# codec_CS42448_rev_A.net
KiCad netlist of a schematic drawn in EAGLE
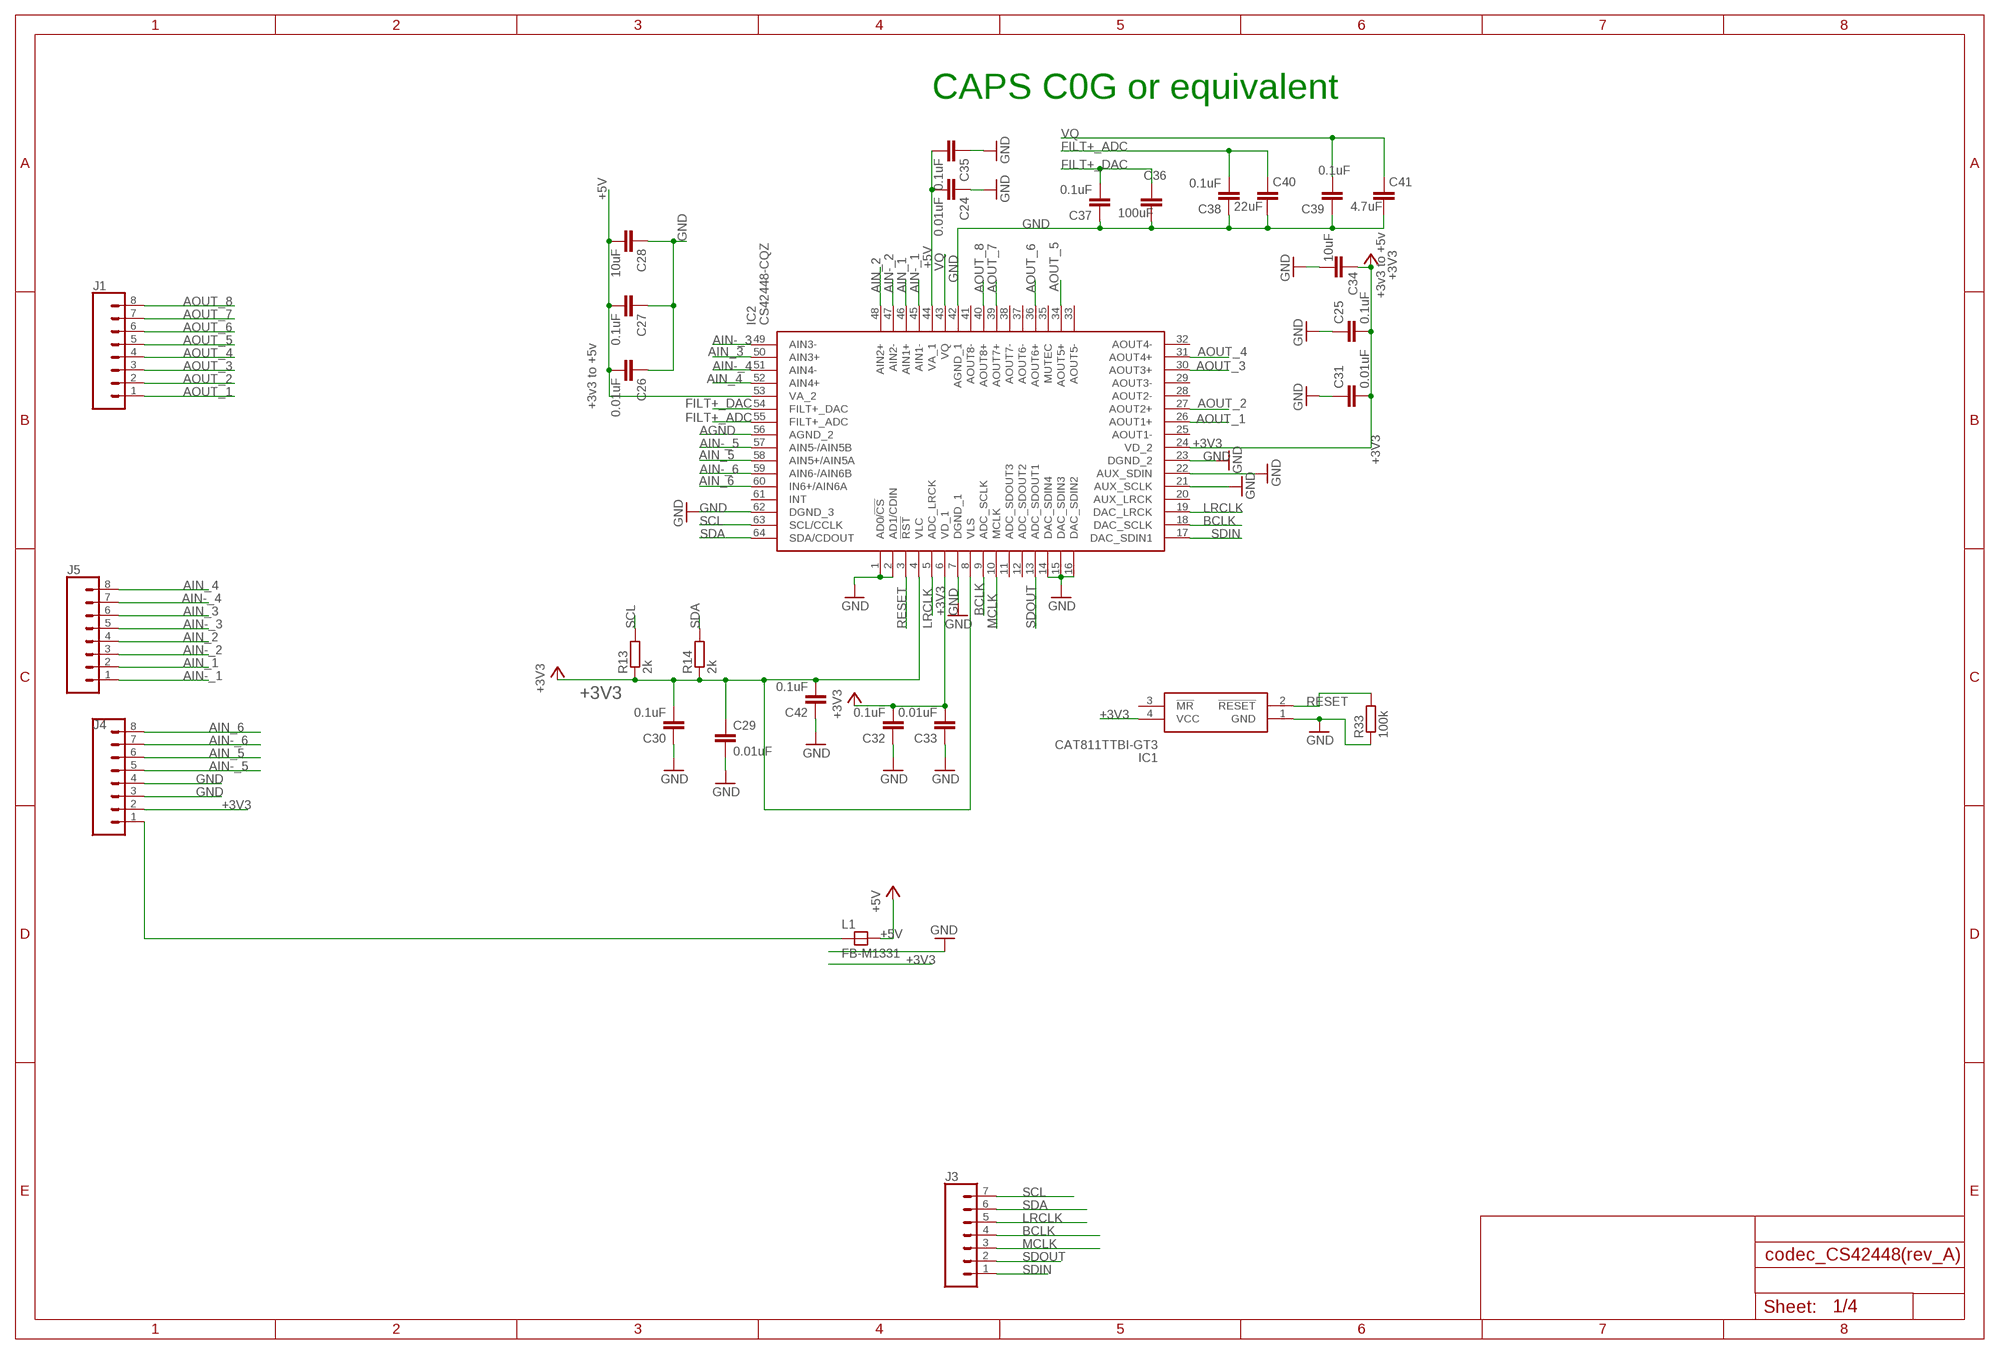
[diagram p0: schematic, sheet 1]
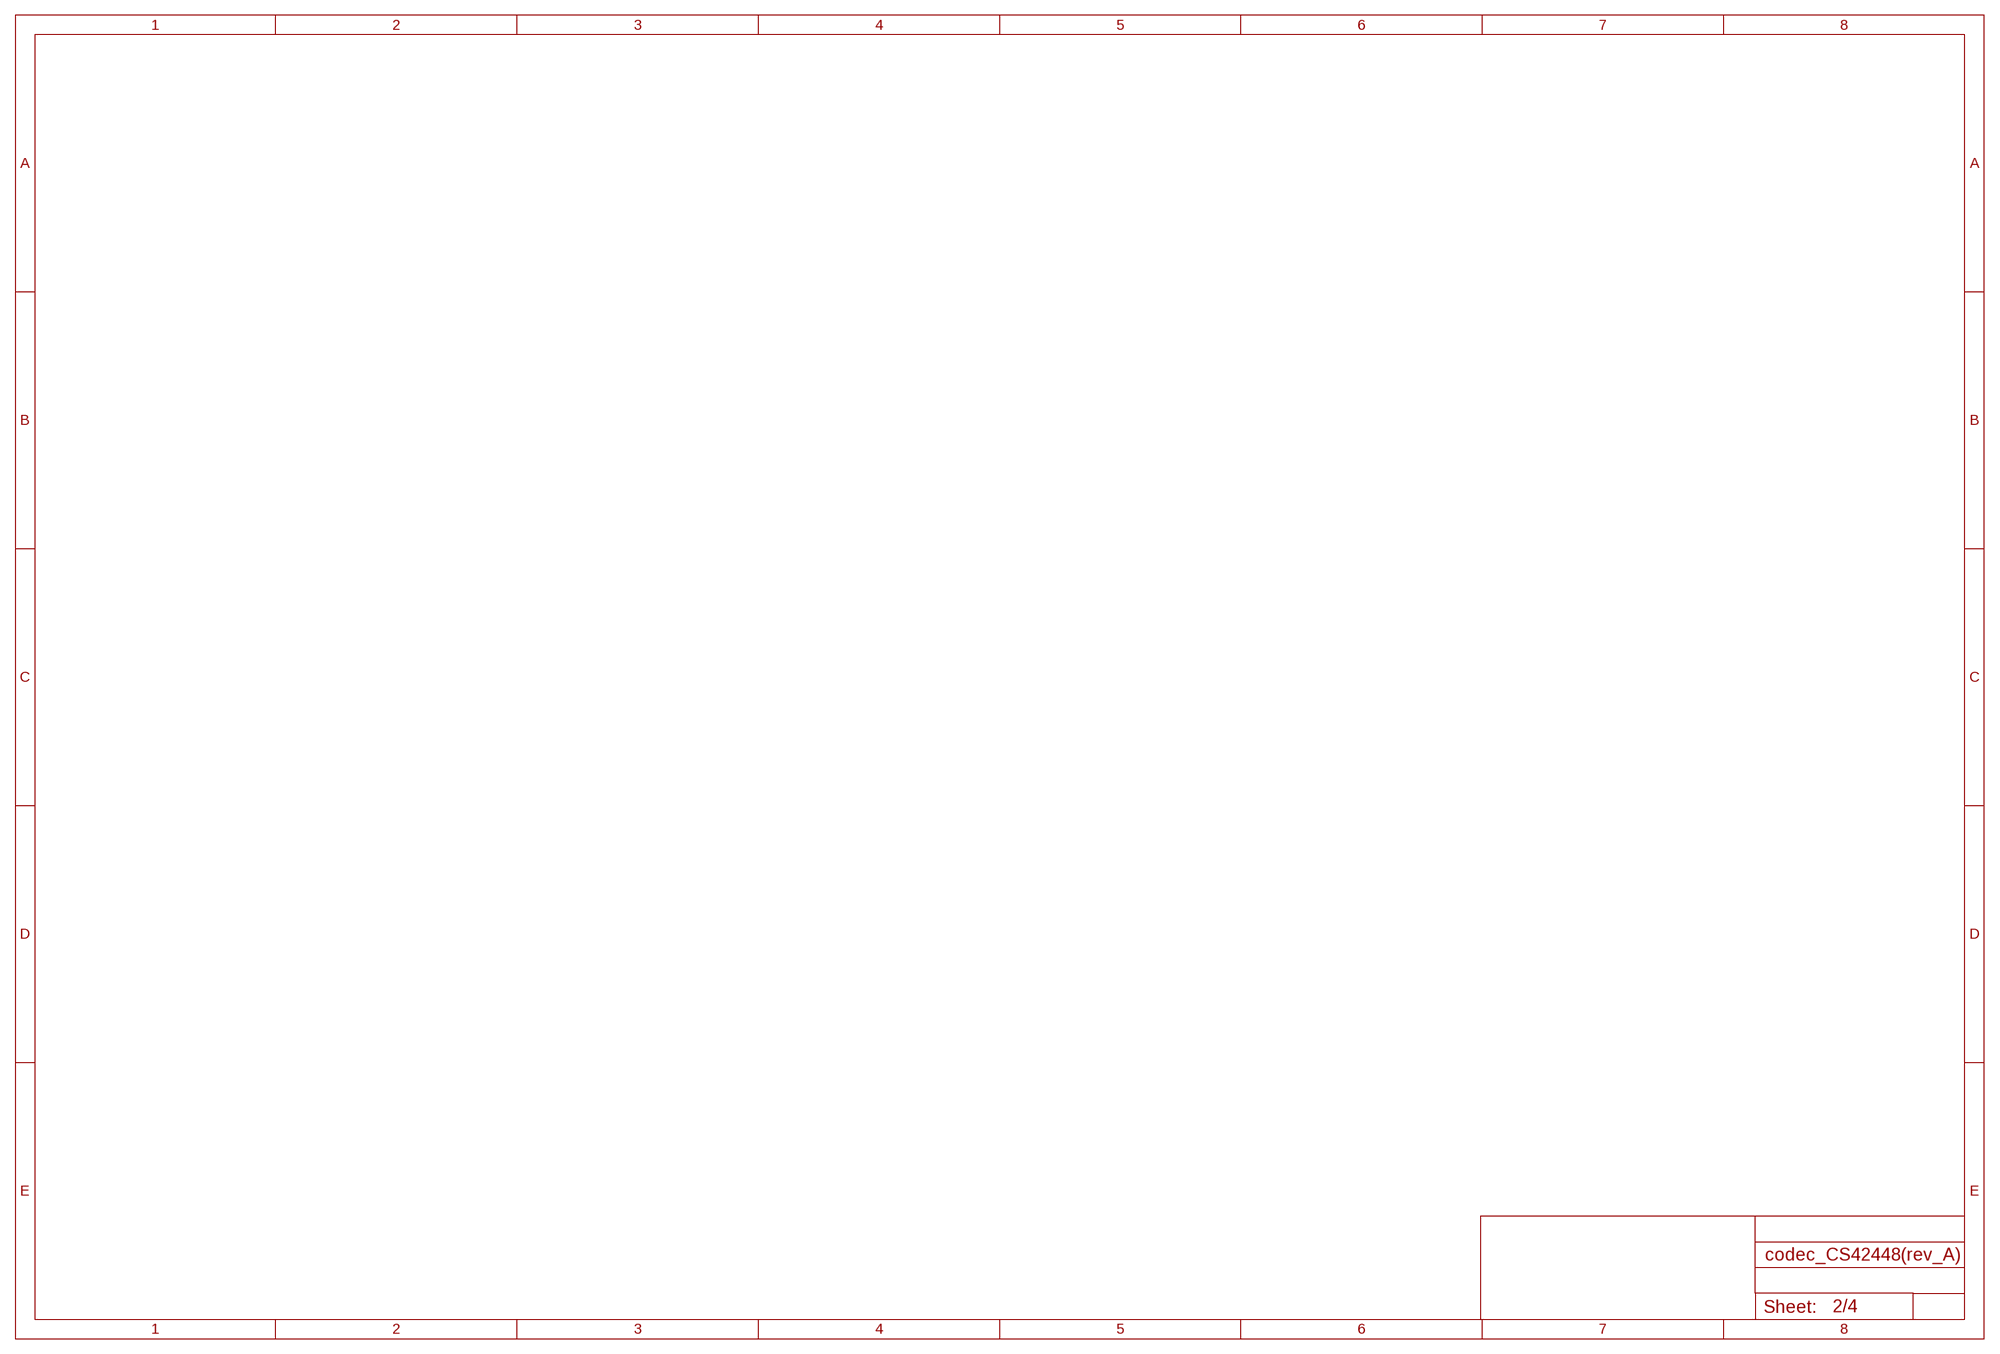
[diagram p1: schematic, sheet 2]
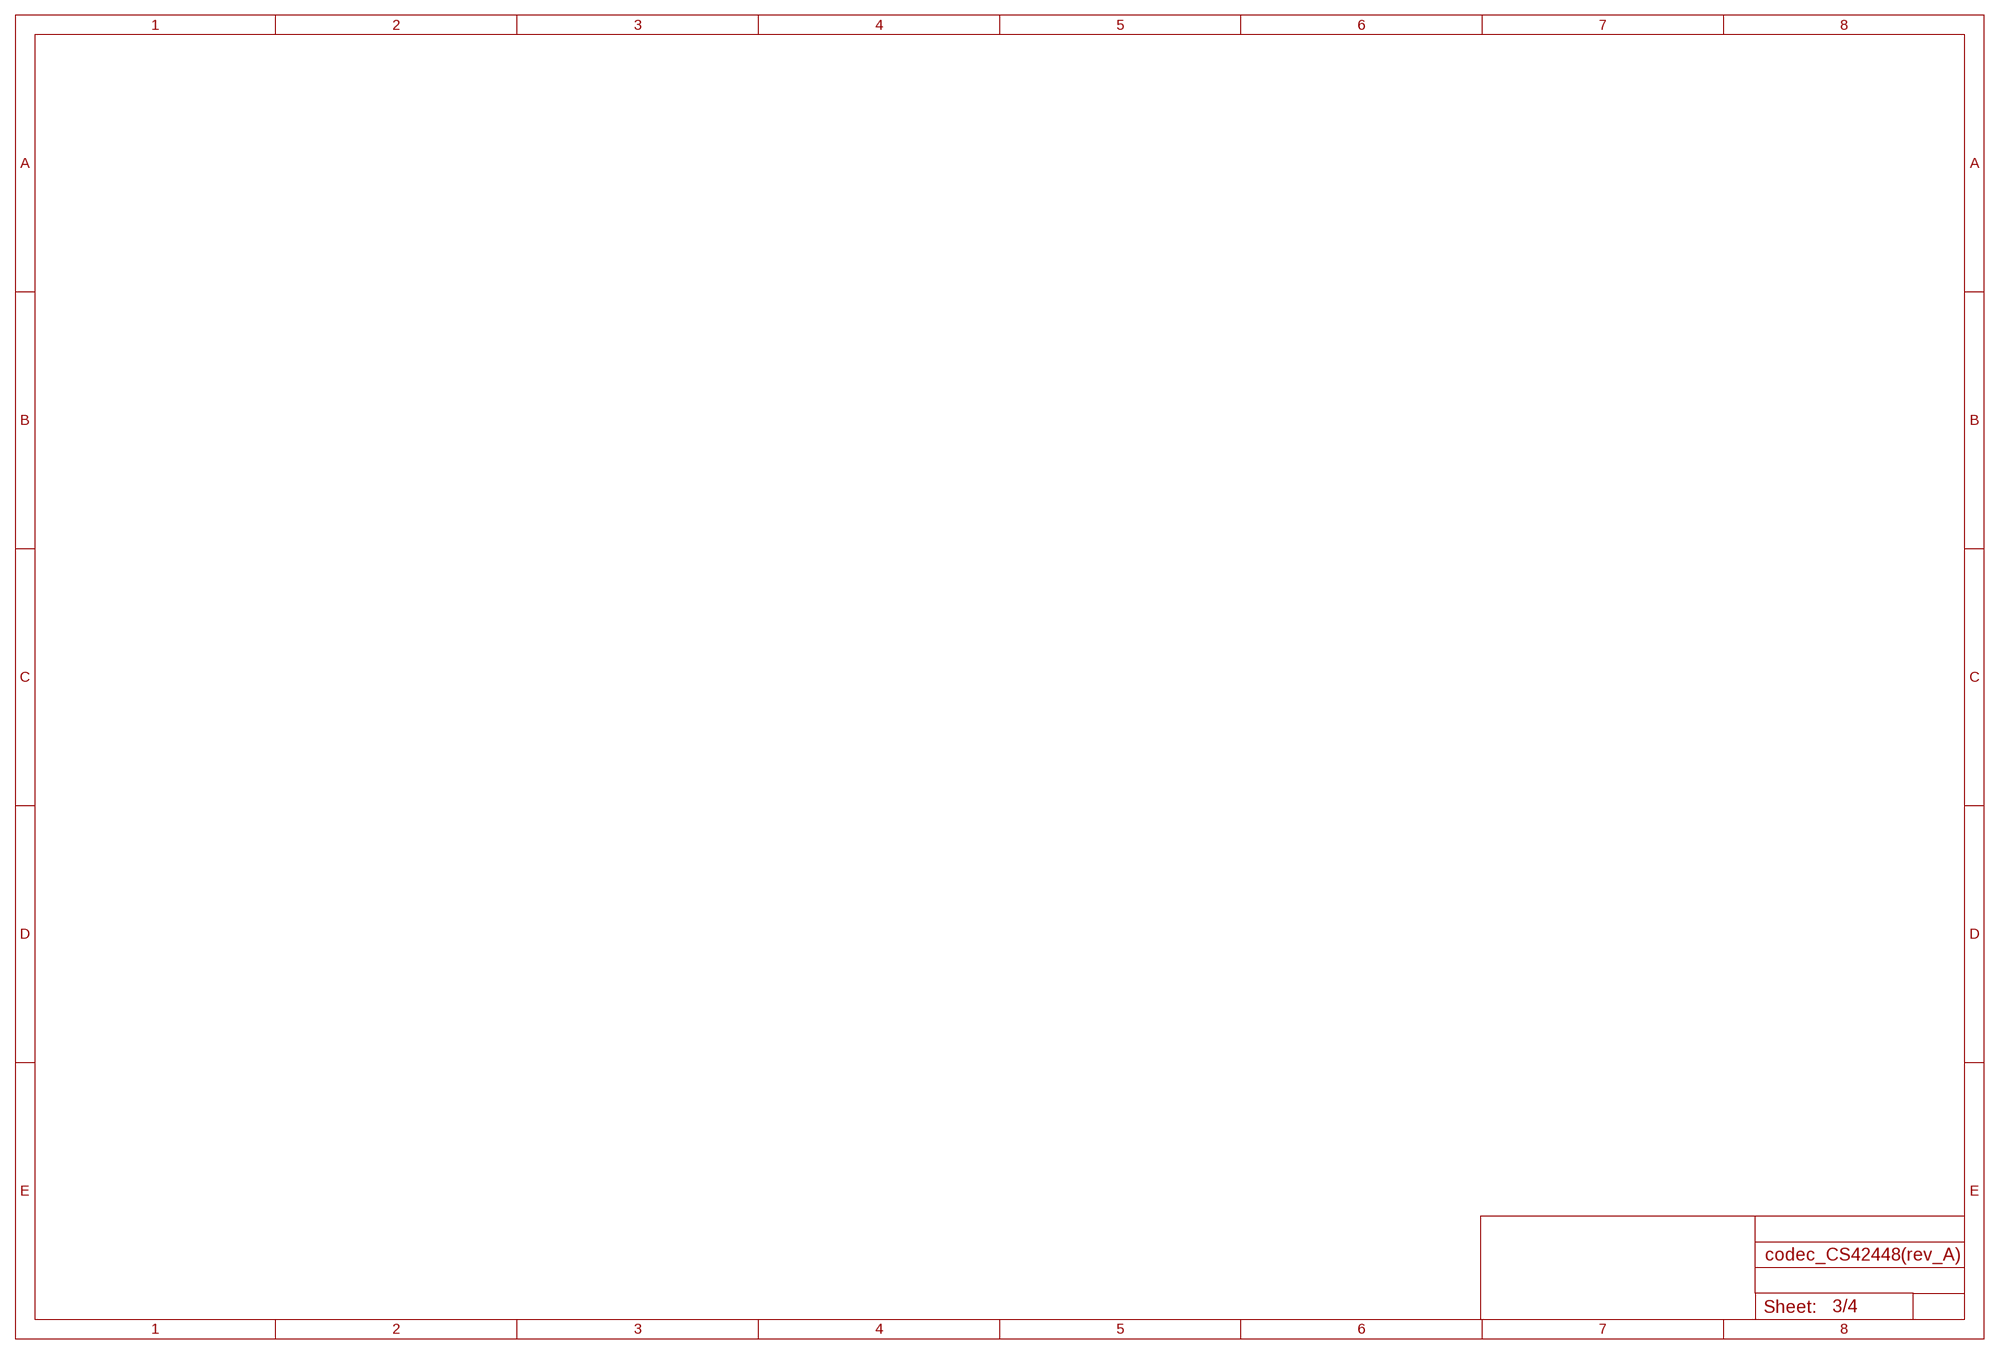
[diagram p2: schematic, sheet 3]
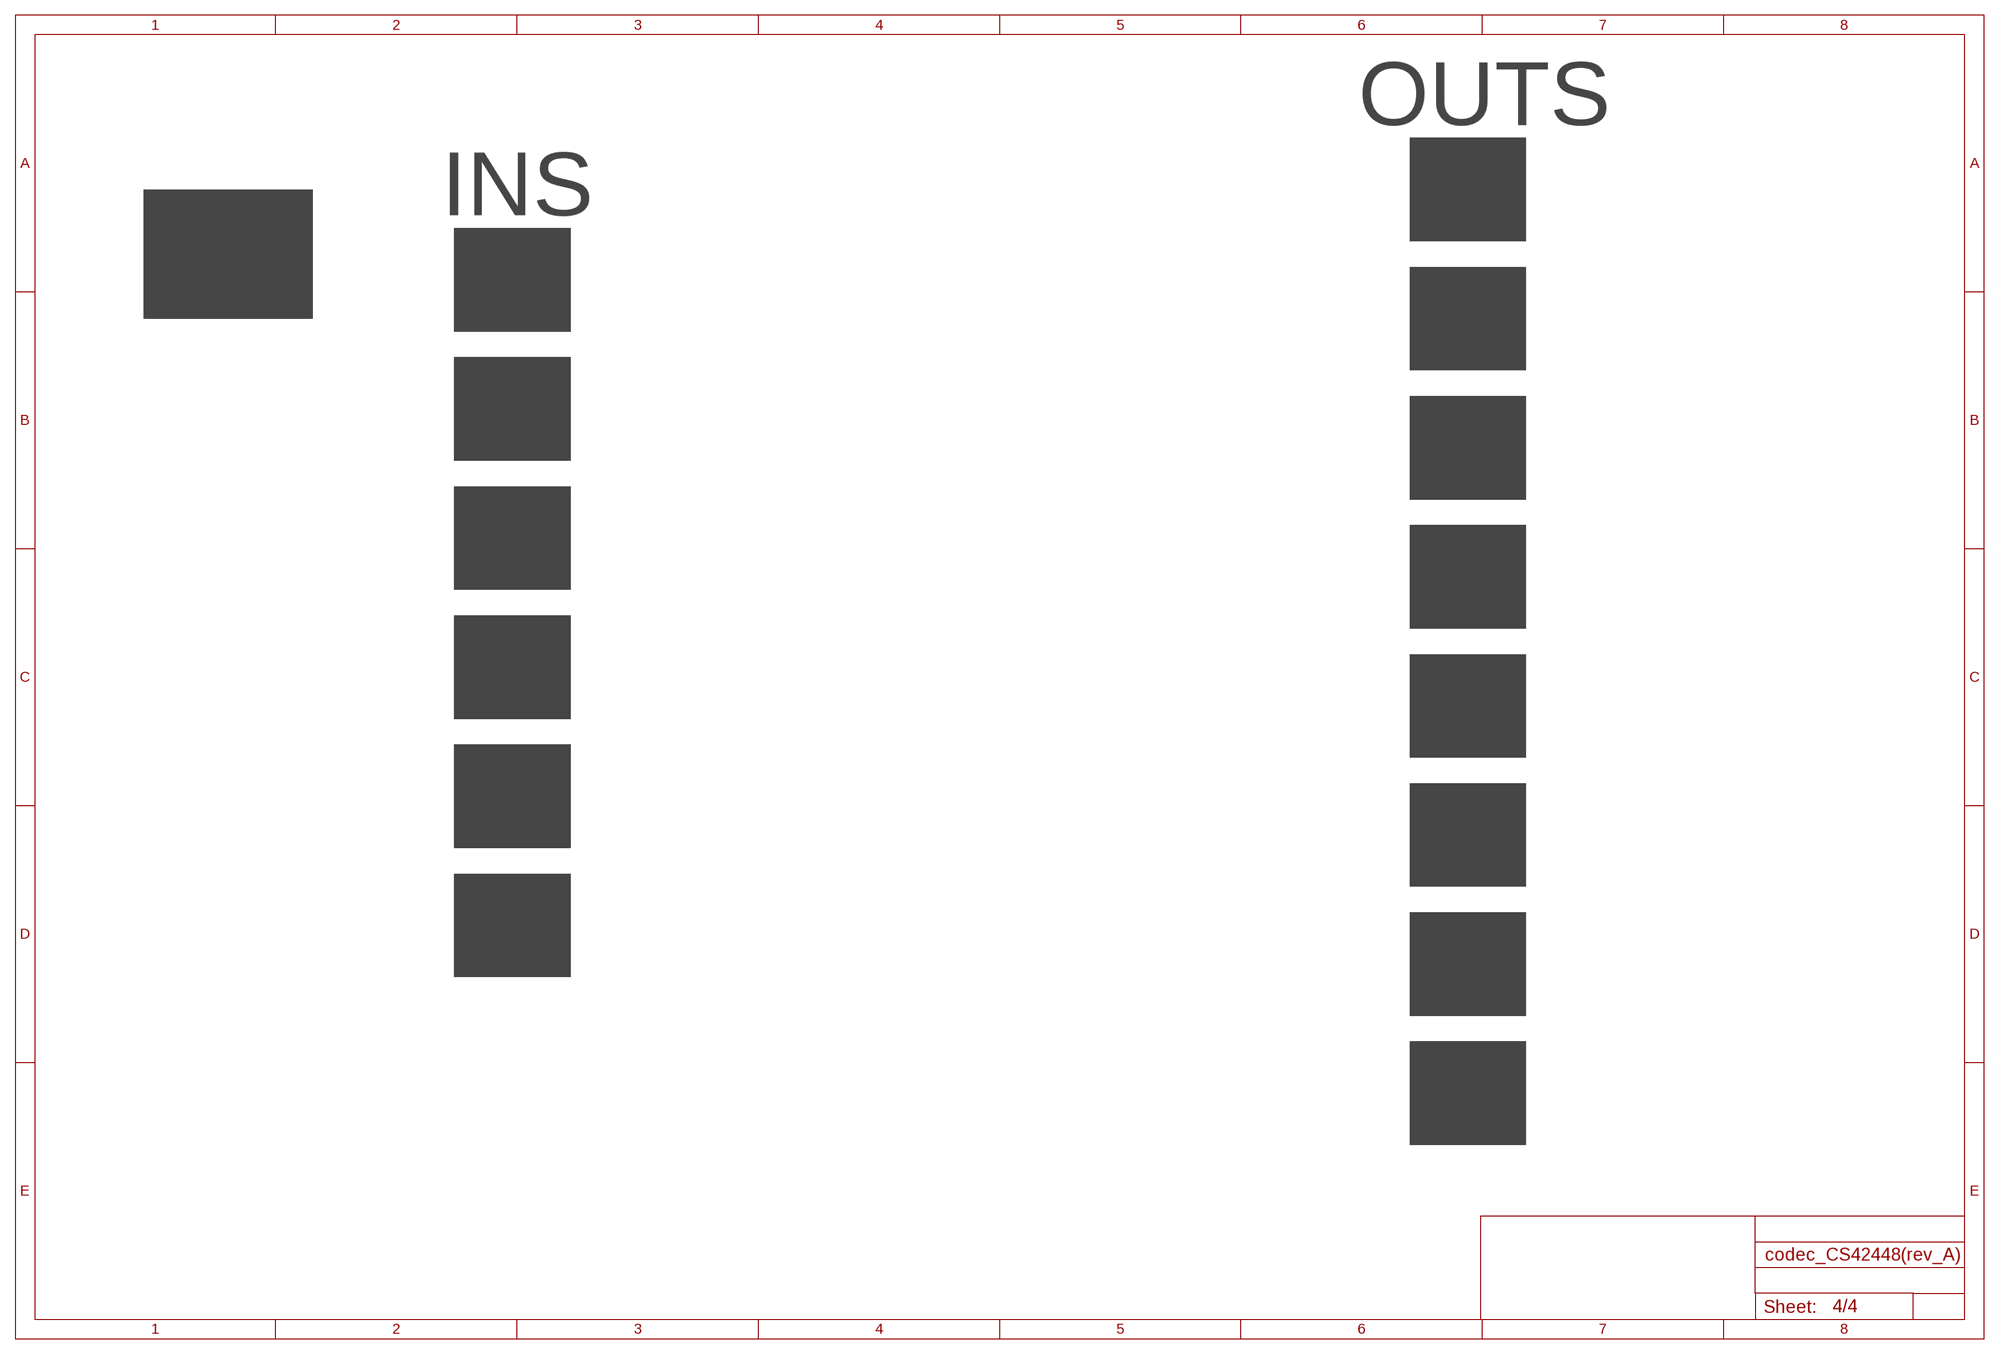
[diagram p3: schematic, sheet 4]

(export (version "E")
  (design (tool "Eeschema 10.0.6"))
  (components
    (comp (ref "C24")
      (value "0.01uF")
      (footprint "eagle-import:C0805")
      (libsource (lib "eagle-import") (part "C-EUC0805"))
    )
    (comp (ref "C25")
      (value "0.1uF")
      (footprint "eagle-import:C0603")
      (libsource (lib "eagle-import") (part "C-EUC0603"))
    )
    (comp (ref "C26")
      (value "0.01uF")
      (footprint "eagle-import:C0805")
      (libsource (lib "eagle-import") (part "C-EUC0805"))
    )
    (comp (ref "C27")
      (value "0.1uF")
      (footprint "eagle-import:C0603")
      (libsource (lib "eagle-import") (part "C-EUC0603"))
    )
    (comp (ref "C28")
      (value "10uF")
      (footprint "eagle-import:C0805")
      (libsource (lib "eagle-import") (part "C-EUC0805"))
    )
    (comp (ref "C29")
      (value "0.01uF")
      (footprint "eagle-import:C0805")
      (libsource (lib "eagle-import") (part "C-EUC0805"))
    )
    (comp (ref "C30")
      (value "0.1uF")
      (footprint "eagle-import:C0603")
      (libsource (lib "eagle-import") (part "C-EUC0603"))
    )
    (comp (ref "C31")
      (value "0.01uF")
      (footprint "eagle-import:C0805")
      (libsource (lib "eagle-import") (part "C-EUC0805"))
    )
    (comp (ref "C32")
      (value "0.1uF")
      (footprint "eagle-import:C0603")
      (libsource (lib "eagle-import") (part "C-EUC0603"))
    )
    (comp (ref "C33")
      (value "0.01uF")
      (footprint "eagle-import:C0805")
      (libsource (lib "eagle-import") (part "C-EUC0805"))
    )
    (comp (ref "C34")
      (value "10uF")
      (footprint "eagle-import:C0805")
      (libsource (lib "eagle-import") (part "C-EUC0805"))
    )
    (comp (ref "C35")
      (value "0.1uF")
      (footprint "eagle-import:C0603")
      (libsource (lib "eagle-import") (part "C-EUC0603"))
    )
    (comp (ref "C36")
      (value "100uF")
      (footprint "eagle-import:C1206")
      (libsource (lib "eagle-import") (part "C-EUC1206"))
    )
    (comp (ref "C37")
      (value "0.1uF")
      (footprint "eagle-import:C0603")
      (libsource (lib "eagle-import") (part "C-EUC0603"))
    )
    (comp (ref "C38")
      (value "0.1uF")
      (footprint "eagle-import:C0603")
      (libsource (lib "eagle-import") (part "C-EUC0603"))
    )
    (comp (ref "C39")
      (value "0.1uF")
      (footprint "eagle-import:C0603")
      (libsource (lib "eagle-import") (part "C-EUC0603"))
    )
    (comp (ref "C40")
      (value "22uF")
      (footprint "eagle-import:C0805")
      (libsource (lib "eagle-import") (part "C-EUC0805"))
    )
    (comp (ref "C41")
      (value "4.7uF")
      (footprint "eagle-import:C0805")
      (libsource (lib "eagle-import") (part "C-EUC0805"))
    )
    (comp (ref "C42")
      (value "0.1uF")
      (footprint "eagle-import:C0805")
      (libsource (lib "eagle-import") (part "C-EUC0805"))
    )
    (comp (ref "IC1")
      (value "CAT811TTBI-GT3")
      (footprint "eagle-import:4-PIN-SOT-143(BI-SUFFIX-CASE-5")
      (fields (field (name "MOUSER_PART_NUMBER") "698-CAT811TTBI-GT3"))
      (libsource (lib "eagle-import") (part "CAT811TTBI-GT3"))
    )
    (comp (ref "IC2")
      (value "CS42448-CQZ")
      (footprint "eagle-import:QFP50P1200X1200X160-64N")
      (fields (field (name "MOUSER_PART_NUMBER") "777-CS42448-CQZ"))
      (libsource (lib "eagle-import") (part "CS42448-CQZ"))
    )
    (comp (ref "J1")
      (value "CONN_08\"")
      (footprint "eagle-import:1X08")
      (libsource (lib "eagle-import") (part "CONN_08{dblquote}"))
    )
    (comp (ref "J3")
      (value "CONN_07")
      (footprint "eagle-import:1X07")
      (libsource (lib "eagle-import") (part "CONN_07"))
    )
    (comp (ref "J4")
      (value "CONN_08\"")
      (footprint "eagle-import:1X08")
      (libsource (lib "eagle-import") (part "CONN_08{dblquote}"))
    )
    (comp (ref "J5")
      (value "CONN_08\"")
      (footprint "eagle-import:1X08")
      (libsource (lib "eagle-import") (part "CONN_08{dblquote}"))
    )
    (comp (ref "L1")
      (value "FB-M1331")
      (footprint "eagle-import:M1331")
      (libsource (lib "eagle-import") (part "FB-M1331"))
    )
    (comp (ref "R13")
      (value "2k")
      (footprint "eagle-import:R0603")
      (libsource (lib "eagle-import") (part "R-EU_R0603"))
    )
    (comp (ref "R14")
      (value "2k")
      (footprint "eagle-import:R0603")
      (libsource (lib "eagle-import") (part "R-EU_R0603"))
    )
    (comp (ref "R33")
      (value "100k")
      (footprint "eagle-import:R0603")
      (libsource (lib "eagle-import") (part "R-EU_R0603"))
    )
  )
  (nets
    (net (code "1") (name "+3V3") (class "Default")
      (node (ref "C25") (pin "2") (pinfunction "2_2") (pintype "passive"))
      (node (ref "C29") (pin "1") (pinfunction "1_1") (pintype "passive"))
      (node (ref "C30") (pin "2") (pinfunction "2_2") (pintype "passive"))
      (node (ref "C31") (pin "2") (pinfunction "2_2") (pintype "passive"))
      (node (ref "C32") (pin "2") (pinfunction "2_2") (pintype "passive"))
      (node (ref "C33") (pin "2") (pinfunction "2_2") (pintype "passive"))
      (node (ref "C34") (pin "1") (pinfunction "1_1") (pintype "passive"))
      (node (ref "C42") (pin "2") (pinfunction "2_2") (pintype "passive"))
      (node (ref "IC1") (pin "4") (pinfunction "VCC_4") (pintype "power_in"))
      (node (ref "IC2") (pin "24") (pinfunction "VD_2_24") (pintype "bidirectional"))
      (node (ref "IC2") (pin "4") (pinfunction "VLC_4") (pintype "bidirectional"))
      (node (ref "IC2") (pin "6") (pinfunction "VD_1_6") (pintype "bidirectional"))
      (node (ref "IC2") (pin "8") (pinfunction "VLS_8") (pintype "bidirectional"))
      (node (ref "J4") (pin "2") (pinfunction "2_2") (pintype "passive"))
      (node (ref "R13") (pin "1") (pinfunction "1_1") (pintype "passive"))
      (node (ref "R14") (pin "1") (pinfunction "1_1") (pintype "passive"))
    )
    (net (code "2") (name "+5V") (class "Default")
      (node (ref "C24") (pin "2") (pinfunction "2_2") (pintype "passive"))
      (node (ref "C26") (pin "2") (pinfunction "2_2") (pintype "passive"))
      (node (ref "C27") (pin "2") (pinfunction "2_2") (pintype "passive"))
      (node (ref "C28") (pin "2") (pinfunction "2_2") (pintype "passive"))
      (node (ref "C35") (pin "2") (pinfunction "2_2") (pintype "passive"))
      (node (ref "IC2") (pin "44") (pinfunction "VA_1_44") (pintype "bidirectional"))
      (node (ref "IC2") (pin "53") (pinfunction "VA_2_53") (pintype "bidirectional"))
      (node (ref "L1") (pin "2") (pinfunction "2_2") (pintype "passive"))
    )
    (net (code "3") (name "AGND") (class "Default")
      (node (ref "IC2") (pin "56") (pinfunction "AGND_2_56") (pintype "bidirectional"))
    )
    (net (code "4") (name "AIN-_1") (class "Default")
      (node (ref "IC2") (pin "45") (pinfunction "AIN1-_45") (pintype "bidirectional"))
      (node (ref "J5") (pin "1") (pinfunction "1_1") (pintype "passive"))
    )
    (net (code "5") (name "AIN-_2") (class "Default")
      (node (ref "IC2") (pin "47") (pinfunction "AIN2-_47") (pintype "bidirectional"))
      (node (ref "J5") (pin "3") (pinfunction "3_3") (pintype "passive"))
    )
    (net (code "6") (name "AIN-_3") (class "Default")
      (node (ref "IC2") (pin "49") (pinfunction "AIN3-_49") (pintype "bidirectional"))
      (node (ref "J5") (pin "5") (pinfunction "5_5") (pintype "passive"))
    )
    (net (code "7") (name "AIN-_4") (class "Default")
      (node (ref "IC2") (pin "51") (pinfunction "AIN4-_51") (pintype "bidirectional"))
      (node (ref "J5") (pin "7") (pinfunction "7_7") (pintype "passive"))
    )
    (net (code "8") (name "AIN-_5") (class "Default")
      (node (ref "IC2") (pin "57") (pinfunction "AIN5-/AIN5B_57") (pintype "bidirectional"))
      (node (ref "J4") (pin "5") (pinfunction "5_5") (pintype "passive"))
    )
    (net (code "9") (name "AIN-_6") (class "Default")
      (node (ref "IC2") (pin "59") (pinfunction "AIN6-/AIN6B_59") (pintype "bidirectional"))
      (node (ref "J4") (pin "7") (pinfunction "7_7") (pintype "passive"))
    )
    (net (code "10") (name "AIN_1") (class "Default")
      (node (ref "IC2") (pin "46") (pinfunction "AIN1+_46") (pintype "bidirectional"))
      (node (ref "J5") (pin "2") (pinfunction "2_2") (pintype "passive"))
    )
    (net (code "11") (name "AIN_2") (class "Default")
      (node (ref "IC2") (pin "48") (pinfunction "AIN2+_48") (pintype "bidirectional"))
      (node (ref "J5") (pin "4") (pinfunction "4_4") (pintype "passive"))
    )
    (net (code "12") (name "AIN_3") (class "Default")
      (node (ref "IC2") (pin "50") (pinfunction "AIN3+_50") (pintype "bidirectional"))
      (node (ref "J5") (pin "6") (pinfunction "6_6") (pintype "passive"))
    )
    (net (code "13") (name "AIN_4") (class "Default")
      (node (ref "IC2") (pin "52") (pinfunction "AIN4+_52") (pintype "bidirectional"))
      (node (ref "J5") (pin "8") (pinfunction "8_8") (pintype "passive"))
    )
    (net (code "14") (name "AIN_5") (class "Default")
      (node (ref "IC2") (pin "58") (pinfunction "AIN5+/AIN5A_58") (pintype "bidirectional"))
      (node (ref "J4") (pin "6") (pinfunction "6_6") (pintype "passive"))
    )
    (net (code "15") (name "AIN_6") (class "Default")
      (node (ref "IC2") (pin "60") (pinfunction "IN6+/AIN6A_60") (pintype "bidirectional"))
      (node (ref "J4") (pin "8") (pinfunction "8_8") (pintype "passive"))
    )
    (net (code "16") (name "AOUT_1") (class "Default")
      (node (ref "IC2") (pin "26") (pinfunction "AOUT1+_26") (pintype "bidirectional"))
      (node (ref "J1") (pin "1") (pinfunction "1_1") (pintype "passive"))
    )
    (net (code "17") (name "AOUT_2") (class "Default")
      (node (ref "IC2") (pin "27") (pinfunction "AOUT2+_27") (pintype "bidirectional"))
      (node (ref "J1") (pin "2") (pinfunction "2_2") (pintype "passive"))
    )
    (net (code "18") (name "AOUT_3") (class "Default")
      (node (ref "IC2") (pin "30") (pinfunction "AOUT3+_30") (pintype "bidirectional"))
      (node (ref "J1") (pin "3") (pinfunction "3_3") (pintype "passive"))
    )
    (net (code "19") (name "AOUT_4") (class "Default")
      (node (ref "IC2") (pin "31") (pinfunction "AOUT4+_31") (pintype "bidirectional"))
      (node (ref "J1") (pin "4") (pinfunction "4_4") (pintype "passive"))
    )
    (net (code "20") (name "AOUT_5") (class "Default")
      (node (ref "IC2") (pin "34") (pinfunction "AOUT5+_34") (pintype "bidirectional"))
      (node (ref "J1") (pin "5") (pinfunction "5_5") (pintype "passive"))
    )
    (net (code "21") (name "AOUT_6") (class "Default")
      (node (ref "IC2") (pin "36") (pinfunction "AOUT6+_36") (pintype "bidirectional"))
      (node (ref "J1") (pin "6") (pinfunction "6_6") (pintype "passive"))
    )
    (net (code "22") (name "AOUT_7") (class "Default")
      (node (ref "IC2") (pin "39") (pinfunction "AOUT7+_39") (pintype "bidirectional"))
      (node (ref "J1") (pin "7") (pinfunction "7_7") (pintype "passive"))
    )
    (net (code "23") (name "AOUT_8") (class "Default")
      (node (ref "IC2") (pin "40") (pinfunction "AOUT8+_40") (pintype "bidirectional"))
      (node (ref "J1") (pin "8") (pinfunction "8_8") (pintype "passive"))
    )
    (net (code "24") (name "BCLK") (class "Default")
      (node (ref "IC2") (pin "18") (pinfunction "DAC_SCLK_18") (pintype "bidirectional"))
      (node (ref "IC2") (pin "9") (pinfunction "ADC_SCLK_9") (pintype "bidirectional"))
      (node (ref "J3") (pin "4") (pinfunction "4_4") (pintype "passive"))
    )
    (net (code "25") (name "FILT+_ADC") (class "Default")
      (node (ref "C38") (pin "2") (pinfunction "2_2") (pintype "passive"))
      (node (ref "C40") (pin "1") (pinfunction "1_1") (pintype "passive"))
      (node (ref "IC2") (pin "55") (pinfunction "FILT+_ADC_55") (pintype "bidirectional"))
    )
    (net (code "26") (name "FILT+_DAC") (class "Default")
      (node (ref "C36") (pin "1") (pinfunction "1_1") (pintype "passive"))
      (node (ref "C37") (pin "2") (pinfunction "2_2") (pintype "passive"))
      (node (ref "IC2") (pin "54") (pinfunction "FILT+_DAC_54") (pintype "bidirectional"))
    )
    (net (code "27") (name "GND") (class "Default")
      (node (ref "C24") (pin "1") (pinfunction "1_1") (pintype "passive"))
      (node (ref "C25") (pin "1") (pinfunction "1_1") (pintype "passive"))
      (node (ref "C26") (pin "1") (pinfunction "1_1") (pintype "passive"))
      (node (ref "C27") (pin "1") (pinfunction "1_1") (pintype "passive"))
      (node (ref "C28") (pin "1") (pinfunction "1_1") (pintype "passive"))
      (node (ref "C29") (pin "2") (pinfunction "2_2") (pintype "passive"))
      (node (ref "C30") (pin "1") (pinfunction "1_1") (pintype "passive"))
      (node (ref "C31") (pin "1") (pinfunction "1_1") (pintype "passive"))
      (node (ref "C32") (pin "1") (pinfunction "1_1") (pintype "passive"))
      (node (ref "C33") (pin "1") (pinfunction "1_1") (pintype "passive"))
      (node (ref "C34") (pin "2") (pinfunction "2_2") (pintype "passive"))
      (node (ref "C35") (pin "1") (pinfunction "1_1") (pintype "passive"))
      (node (ref "C36") (pin "2") (pinfunction "2_2") (pintype "passive"))
      (node (ref "C37") (pin "1") (pinfunction "1_1") (pintype "passive"))
      (node (ref "C38") (pin "1") (pinfunction "1_1") (pintype "passive"))
      (node (ref "C39") (pin "1") (pinfunction "1_1") (pintype "passive"))
      (node (ref "C40") (pin "2") (pinfunction "2_2") (pintype "passive"))
      (node (ref "C41") (pin "2") (pinfunction "2_2") (pintype "passive"))
      (node (ref "C42") (pin "1") (pinfunction "1_1") (pintype "passive"))
      (node (ref "IC1") (pin "1") (pinfunction "GND_1") (pintype "power_in"))
      (node (ref "IC2") (pin "1") (pinfunction "AD0/~{CS}_1") (pintype "bidirectional"))
      (node (ref "IC2") (pin "14") (pinfunction "DAC_SDIN4_14") (pintype "bidirectional"))
      (node (ref "IC2") (pin "15") (pinfunction "DAC_SDIN3_15") (pintype "bidirectional"))
      (node (ref "IC2") (pin "16") (pinfunction "DAC_SDIN2_16") (pintype "bidirectional"))
      (node (ref "IC2") (pin "2") (pinfunction "AD1/CDIN_2") (pintype "bidirectional"))
      (node (ref "IC2") (pin "21") (pinfunction "AUX_SCLK_21") (pintype "bidirectional"))
      (node (ref "IC2") (pin "22") (pinfunction "AUX_SDIN_22") (pintype "bidirectional"))
      (node (ref "IC2") (pin "23") (pinfunction "DGND_2_23") (pintype "bidirectional"))
      (node (ref "IC2") (pin "42") (pinfunction "AGND_1_42") (pintype "bidirectional"))
      (node (ref "IC2") (pin "62") (pinfunction "DGND_3_62") (pintype "bidirectional"))
      (node (ref "IC2") (pin "7") (pinfunction "DGND_1_7") (pintype "bidirectional"))
      (node (ref "J4") (pin "3") (pinfunction "3_3") (pintype "passive"))
      (node (ref "J4") (pin "4") (pinfunction "4_4") (pintype "passive"))
      (node (ref "R33") (pin "1") (pinfunction "1_1") (pintype "passive"))
    )
    (net (code "28") (name "LRCLK") (class "Default")
      (node (ref "IC2") (pin "19") (pinfunction "DAC_LRCK_19") (pintype "bidirectional"))
      (node (ref "IC2") (pin "5") (pinfunction "ADC_LRCK_5") (pintype "bidirectional"))
      (node (ref "J3") (pin "5") (pinfunction "5_5") (pintype "passive"))
    )
    (net (code "29") (name "MCLK") (class "Default")
      (node (ref "IC2") (pin "10") (pinfunction "MCLK_10") (pintype "bidirectional"))
      (node (ref "J3") (pin "3") (pinfunction "3_3") (pintype "passive"))
    )
    (net (code "30") (name "Net-(J4-Pad1)") (class "Default")
      (node (ref "J4") (pin "1") (pinfunction "1_1") (pintype "passive"))
      (node (ref "L1") (pin "1") (pinfunction "1_1") (pintype "passive"))
    )
    (net (code "31") (name "RESET") (class "Default")
      (node (ref "IC1") (pin "2") (pinfunction "~{RESET}_2") (pintype "bidirectional"))
      (node (ref "IC2") (pin "3") (pinfunction "~{RST}_3") (pintype "bidirectional"))
      (node (ref "R33") (pin "2") (pinfunction "2_2") (pintype "passive"))
    )
    (net (code "32") (name "SCL") (class "Default")
      (node (ref "IC2") (pin "63") (pinfunction "SCL/CCLK_63") (pintype "bidirectional"))
      (node (ref "J3") (pin "7") (pinfunction "7_7") (pintype "passive"))
      (node (ref "R13") (pin "2") (pinfunction "2_2") (pintype "passive"))
    )
    (net (code "33") (name "SDA") (class "Default")
      (node (ref "IC2") (pin "64") (pinfunction "SDA/CDOUT_64") (pintype "bidirectional"))
      (node (ref "J3") (pin "6") (pinfunction "6_6") (pintype "passive"))
      (node (ref "R14") (pin "2") (pinfunction "2_2") (pintype "passive"))
    )
    (net (code "34") (name "SDIN") (class "Default")
      (node (ref "IC2") (pin "17") (pinfunction "DAC_SDIN1_17") (pintype "bidirectional"))
      (node (ref "J3") (pin "1") (pinfunction "1_1") (pintype "passive"))
    )
    (net (code "35") (name "SDOUT") (class "Default")
      (node (ref "IC2") (pin "13") (pinfunction "ADC_SDOUT1_13") (pintype "bidirectional"))
      (node (ref "J3") (pin "2") (pinfunction "2_2") (pintype "passive"))
    )
    (net (code "36") (name "VQ") (class "Default")
      (node (ref "C39") (pin "2") (pinfunction "2_2") (pintype "passive"))
      (node (ref "C41") (pin "1") (pinfunction "1_1") (pintype "passive"))
      (node (ref "IC2") (pin "43") (pinfunction "VQ_43") (pintype "bidirectional"))
    )
    (net (code "37") (name "unconnected-(IC1-~{MR}-Pad3)") (class "Default")
      (node (ref "IC1") (pin "3") (pinfunction "~{MR}_3") (pintype "bidirectional"))
    )
    (net (code "38") (name "unconnected-(IC2-ADC_SDOUT2-Pad12)") (class "Default")
      (node (ref "IC2") (pin "12") (pinfunction "ADC_SDOUT2_12") (pintype "bidirectional"))
    )
    (net (code "39") (name "unconnected-(IC2-ADC_SDOUT3-Pad11)") (class "Default")
      (node (ref "IC2") (pin "11") (pinfunction "ADC_SDOUT3_11") (pintype "bidirectional"))
    )
    (net (code "40") (name "unconnected-(IC2-AOUT1--Pad25)") (class "Default")
      (node (ref "IC2") (pin "25") (pinfunction "AOUT1-_25") (pintype "bidirectional"))
    )
    (net (code "41") (name "unconnected-(IC2-AOUT2--Pad28)") (class "Default")
      (node (ref "IC2") (pin "28") (pinfunction "AOUT2-_28") (pintype "bidirectional"))
    )
    (net (code "42") (name "unconnected-(IC2-AOUT3--Pad29)") (class "Default")
      (node (ref "IC2") (pin "29") (pinfunction "AOUT3-_29") (pintype "bidirectional"))
    )
    (net (code "43") (name "unconnected-(IC2-AOUT4--Pad32)") (class "Default")
      (node (ref "IC2") (pin "32") (pinfunction "AOUT4-_32") (pintype "bidirectional"))
    )
    (net (code "44") (name "unconnected-(IC2-AOUT5--Pad33)") (class "Default")
      (node (ref "IC2") (pin "33") (pinfunction "AOUT5-_33") (pintype "bidirectional"))
    )
    (net (code "45") (name "unconnected-(IC2-AOUT6--Pad37)") (class "Default")
      (node (ref "IC2") (pin "37") (pinfunction "AOUT6-_37") (pintype "bidirectional"))
    )
    (net (code "46") (name "unconnected-(IC2-AOUT7--Pad38)") (class "Default")
      (node (ref "IC2") (pin "38") (pinfunction "AOUT7-_38") (pintype "bidirectional"))
    )
    (net (code "47") (name "unconnected-(IC2-AOUT8--Pad41)") (class "Default")
      (node (ref "IC2") (pin "41") (pinfunction "AOUT8-_41") (pintype "bidirectional"))
    )
    (net (code "48") (name "unconnected-(IC2-AUX_LRCK-Pad20)") (class "Default")
      (node (ref "IC2") (pin "20") (pinfunction "AUX_LRCK_20") (pintype "bidirectional"))
    )
    (net (code "49") (name "unconnected-(IC2-INT-Pad61)") (class "Default")
      (node (ref "IC2") (pin "61") (pinfunction "INT_61") (pintype "bidirectional"))
    )
    (net (code "50") (name "unconnected-(IC2-MUTEC-Pad35)") (class "Default")
      (node (ref "IC2") (pin "35") (pinfunction "MUTEC_35") (pintype "bidirectional"))
    )
  )
)
